# SMINIPROG.net
KiCad netlist of a schematic drawn in EAGLE
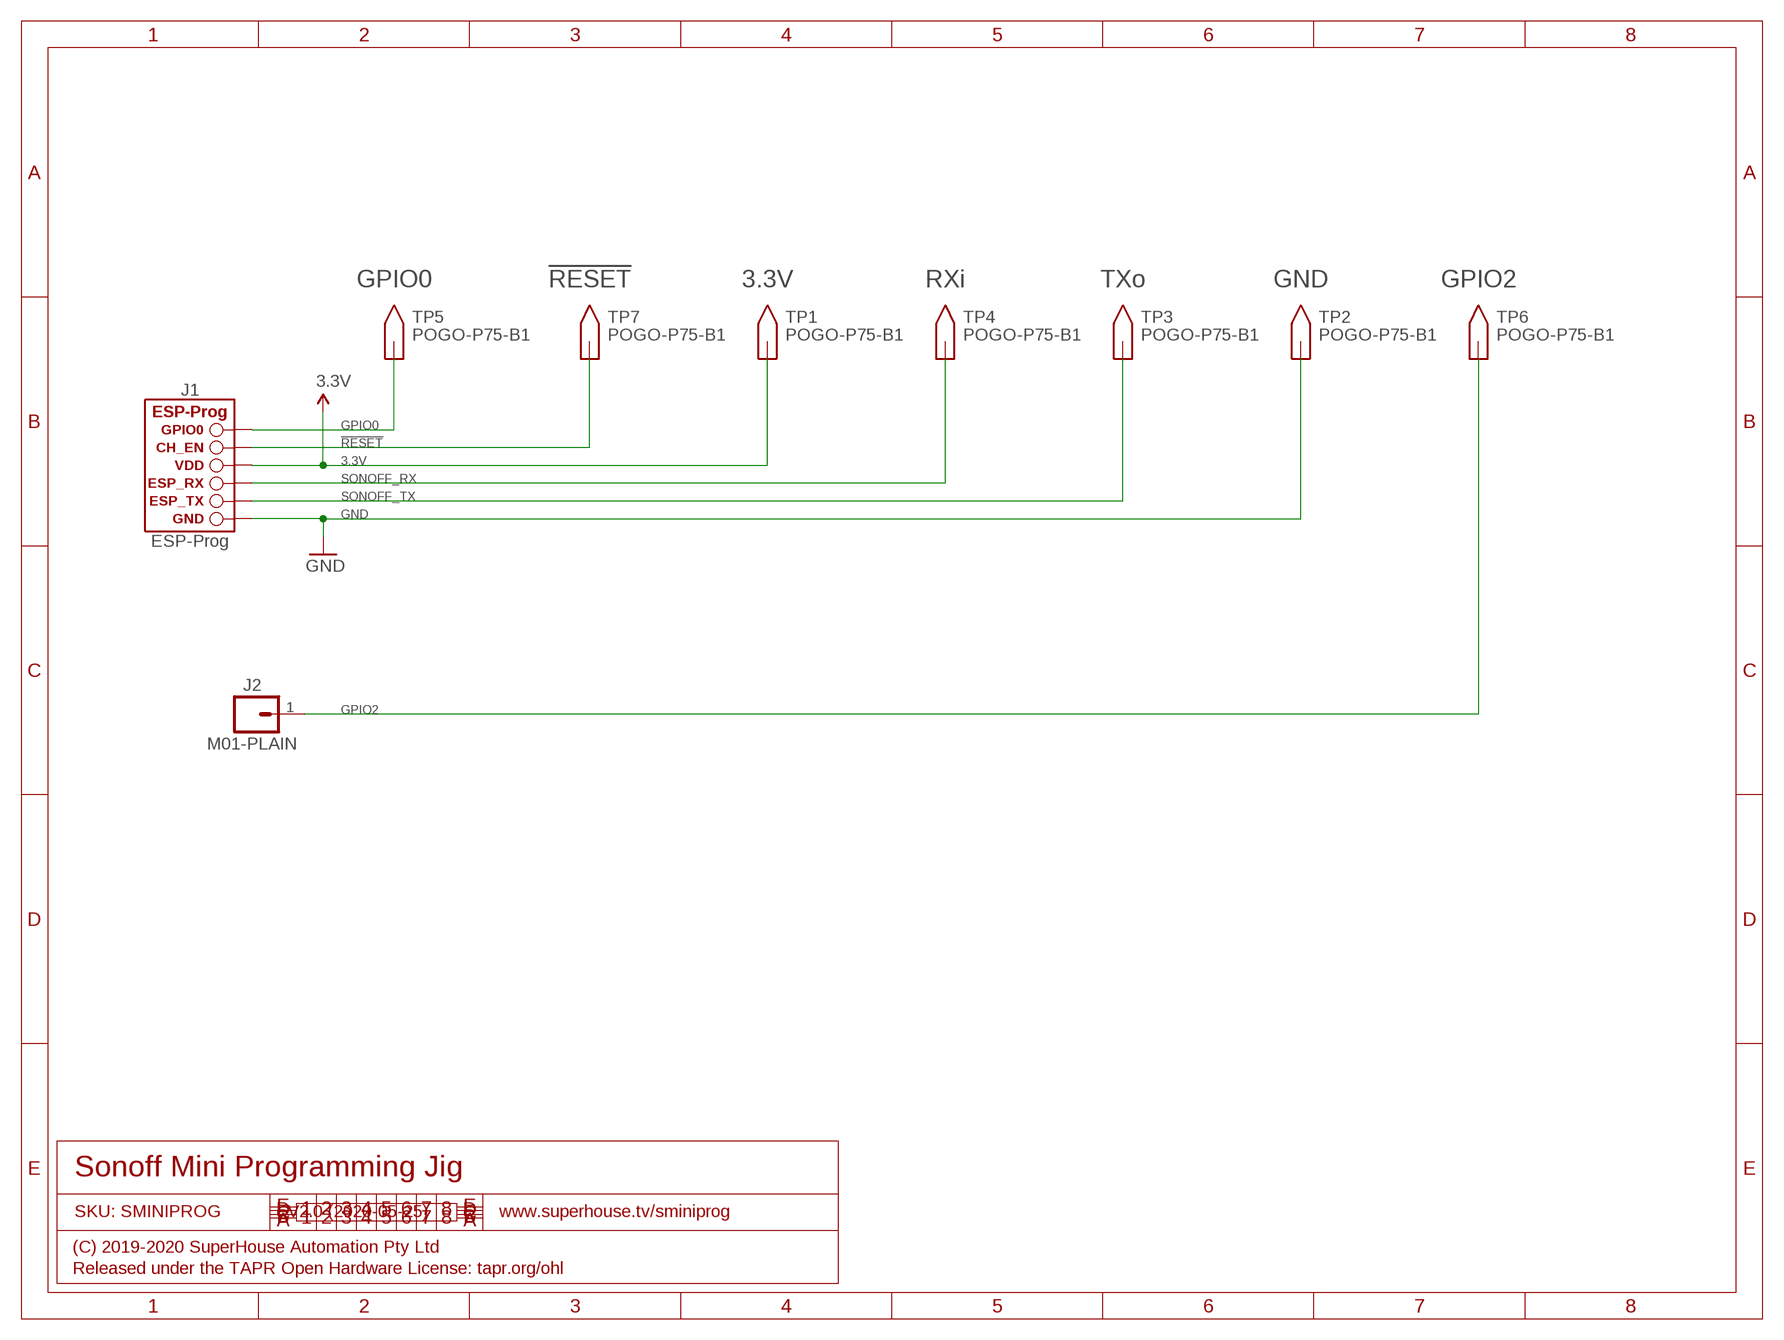
[diagram p0: schematic, sheet 1]

(export (version "E")
  (design (tool "Eeschema 10.0.6"))
  (components
    (comp (ref "J1")
      (value "ESP-PROG-1X6-2.54-SOCKET-RA")
      (footprint "eagle-import:1X6-2.54-SOCKET-RA")
      (libsource (lib "eagle-import") (part "ESP-PROG-1X6-2.54-SOCKET-RA"))
    )
    (comp (ref "J2")
      (value "M01-PLAIN")
      (footprint "eagle-import:1X01")
      (libsource (lib "eagle-import") (part "M01-PLAIN"))
    )
    (comp (ref "TP1")
      (value "POGO-P75-B1")
      (footprint "eagle-import:PIN-1.02")
      (libsource (lib "eagle-import") (part "POGO-P75-B1"))
    )
    (comp (ref "TP2")
      (value "POGO-P75-B1")
      (footprint "eagle-import:PIN-1.02")
      (libsource (lib "eagle-import") (part "POGO-P75-B1"))
    )
    (comp (ref "TP3")
      (value "POGO-P75-B1")
      (footprint "eagle-import:PIN-1.02")
      (libsource (lib "eagle-import") (part "POGO-P75-B1"))
    )
    (comp (ref "TP4")
      (value "POGO-P75-B1")
      (footprint "eagle-import:PIN-1.02")
      (libsource (lib "eagle-import") (part "POGO-P75-B1"))
    )
    (comp (ref "TP5")
      (value "POGO-P75-B1")
      (footprint "eagle-import:PIN-1.02")
      (libsource (lib "eagle-import") (part "POGO-P75-B1"))
    )
    (comp (ref "TP6")
      (value "POGO-P75-B1")
      (footprint "eagle-import:PIN-1.02")
      (libsource (lib "eagle-import") (part "POGO-P75-B1"))
    )
    (comp (ref "TP7")
      (value "POGO-P75-B1")
      (footprint "eagle-import:PIN-1.02")
      (libsource (lib "eagle-import") (part "POGO-P75-B1"))
    )
  )
  (nets
    (net (code "1") (name "/GPIO0") (class "Default")
      (node (ref "J1") (pin "6") (pinfunction "GPIO0_6") (pintype "passive"))
      (node (ref "TP5") (pin "P$1") (pinfunction "P$1_P$1") (pintype "bidirectional"))
    )
    (net (code "2") (name "/GPIO2") (class "Default")
      (node (ref "J2") (pin "1") (pinfunction "1_1") (pintype "passive"))
      (node (ref "TP6") (pin "P$1") (pinfunction "P$1_P$1") (pintype "bidirectional"))
    )
    (net (code "3") (name "/SONOFF_RX") (class "Default")
      (node (ref "J1") (pin "3") (pinfunction "ESP_RX_3") (pintype "passive"))
      (node (ref "TP4") (pin "P$1") (pinfunction "P$1_P$1") (pintype "bidirectional"))
    )
    (net (code "4") (name "/SONOFF_TX") (class "Default")
      (node (ref "J1") (pin "2") (pinfunction "ESP_TX_2") (pintype "passive"))
      (node (ref "TP3") (pin "P$1") (pinfunction "P$1_P$1") (pintype "bidirectional"))
    )
    (net (code "5") (name "/~{RESET}") (class "Default")
      (node (ref "J1") (pin "5") (pinfunction "CH_EN_5") (pintype "passive"))
      (node (ref "TP7") (pin "P$1") (pinfunction "P$1_P$1") (pintype "bidirectional"))
    )
    (net (code "6") (name "3.3V") (class "Default")
      (node (ref "J1") (pin "4") (pinfunction "VDD_4") (pintype "passive"))
      (node (ref "TP1") (pin "P$1") (pinfunction "P$1_P$1") (pintype "bidirectional"))
    )
    (net (code "7") (name "GND") (class "Default")
      (node (ref "J1") (pin "1") (pinfunction "GND_1") (pintype "passive"))
      (node (ref "TP2") (pin "P$1") (pinfunction "P$1_P$1") (pintype "bidirectional"))
    )
  )
)
